# board.net
KiCad netlist of a schematic drawn in EAGLE
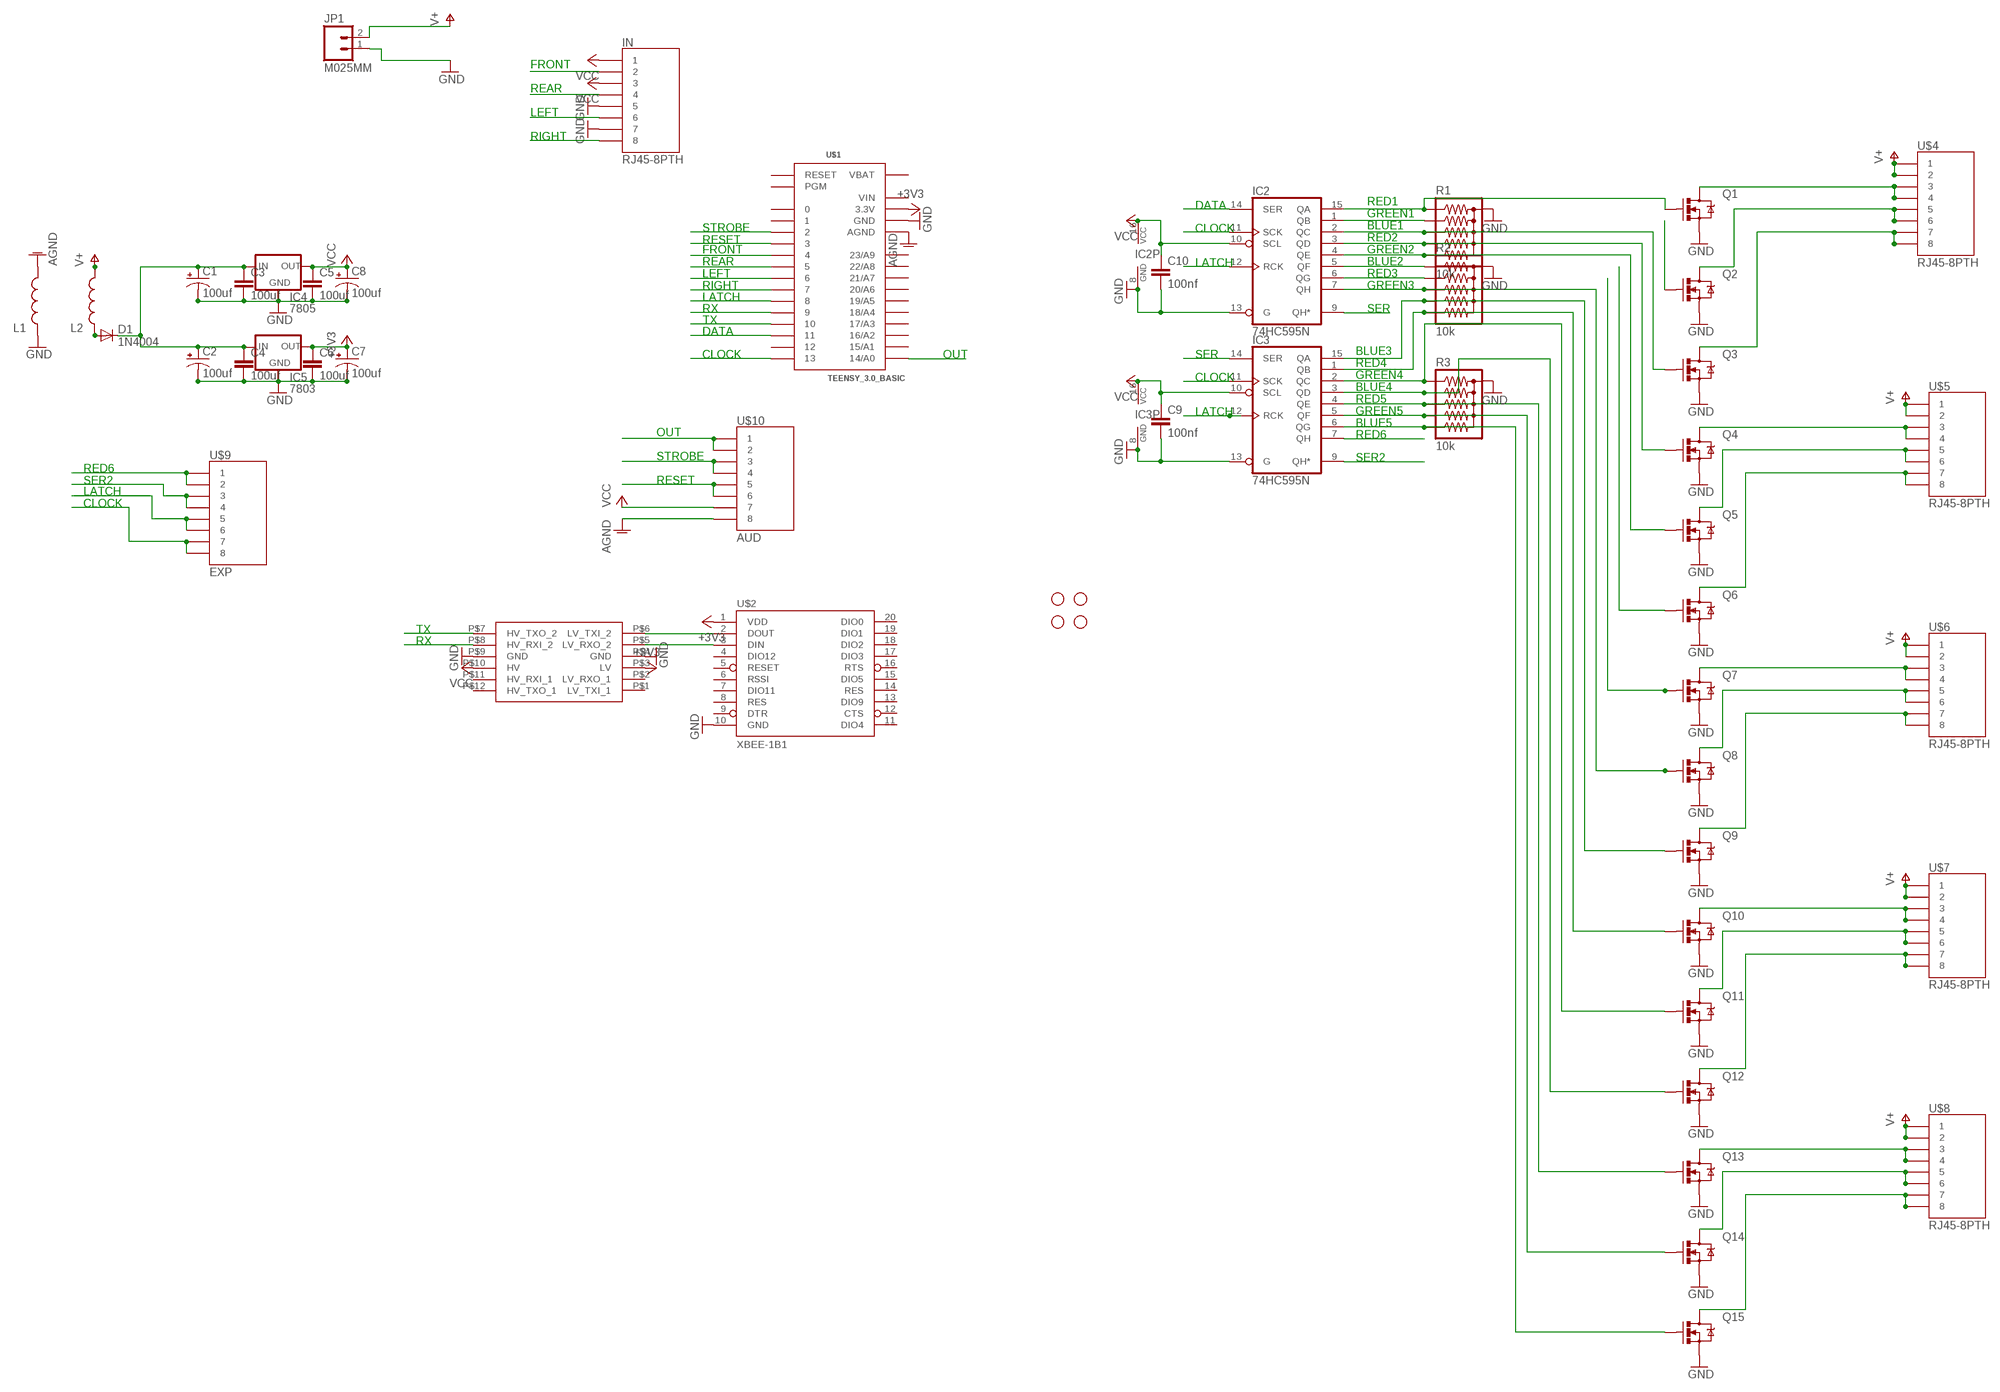
[diagram p0: schematic, sheet 1]

(export (version "E")
  (design (tool "Eeschema 10.0.6"))
  (components
    (comp (ref "C1")
      (value "100uf")
      (footprint "eagle-import:CPOL-RADIAL-100UF-25V")
      (libsource (lib "eagle-import") (part "CAP_POLPTH1"))
    )
    (comp (ref "C2")
      (value "100uf")
      (footprint "eagle-import:CPOL-RADIAL-100UF-25V")
      (libsource (lib "eagle-import") (part "CAP_POLPTH1"))
    )
    (comp (ref "C3")
      (value "100uf")
      (footprint "eagle-import:CAP-PTH-SMALL")
      (libsource (lib "eagle-import") (part "CAPPTH"))
    )
    (comp (ref "C4")
      (value "100uf")
      (footprint "eagle-import:CAP-PTH-SMALL")
      (libsource (lib "eagle-import") (part "CAPPTH"))
    )
    (comp (ref "C5")
      (value "100uf")
      (footprint "eagle-import:CAP-PTH-SMALL")
      (libsource (lib "eagle-import") (part "CAPPTH"))
    )
    (comp (ref "C6")
      (value "100uf")
      (footprint "eagle-import:CAP-PTH-SMALL")
      (libsource (lib "eagle-import") (part "CAPPTH"))
    )
    (comp (ref "C7")
      (value "100uf")
      (footprint "eagle-import:CPOL-RADIAL-100UF-25V")
      (libsource (lib "eagle-import") (part "CAP_POLPTH1"))
    )
    (comp (ref "C8")
      (value "100uf")
      (footprint "eagle-import:CPOL-RADIAL-100UF-25V")
      (libsource (lib "eagle-import") (part "CAP_POLPTH1"))
    )
    (comp (ref "C9")
      (value "100nf")
      (footprint "eagle-import:CAP-PTH-SMALL")
      (libsource (lib "eagle-import") (part "CAPPTH"))
    )
    (comp (ref "C10")
      (value "100nf")
      (footprint "eagle-import:CAP-PTH-SMALL")
      (libsource (lib "eagle-import") (part "CAPPTH"))
    )
    (comp (ref "D1")
      (value "1N4004")
      (footprint "eagle-import:DO41-10")
      (libsource (lib "eagle-import") (part "1N4004"))
    )
    (comp (ref "IC2")
      (value "74HC595N")
      (footprint "eagle-import:DIL16")
      (libsource (lib "eagle-import") (part "74595NHC"))
    )
    (comp (ref "IC3")
      (value "74HC595N")
      (footprint "eagle-import:DIL16")
      (libsource (lib "eagle-import") (part "74595NHC"))
    )
    (comp (ref "IC4")
      (value "7805")
      (footprint "eagle-import:TO220-IGO")
      (libsource (lib "eagle-import") (part "V_REG_78XXSINK"))
    )
    (comp (ref "IC5")
      (value "7803")
      (footprint "eagle-import:78XXL")
      (libsource (lib "eagle-import") (part "V_REG_LD1117VXX"))
    )
    (comp (ref "IN")
      (value "RJ45-8PTH")
      (footprint "eagle-import:RJ45-8")
      (libsource (lib "eagle-import") (part "RJ45-8PTH"))
    )
    (comp (ref "JP1")
      (value "M025MM")
      (footprint "eagle-import:SCREWTERMINAL-5MM-2")
      (libsource (lib "eagle-import") (part "M025MM"))
    )
    (comp (ref "L1")
      (value "INDUCTORRLB0912")
      (footprint "eagle-import:RLB0912")
      (libsource (lib "eagle-import") (part "INDUCTORRLB0912"))
    )
    (comp (ref "L2")
      (value "INDUCTORRLB0912")
      (footprint "eagle-import:RLB0912")
      (libsource (lib "eagle-import") (part "INDUCTORRLB0912"))
    )
    (comp (ref "Q1")
      (value "MOSFET-NCHANNELFQP30N06L")
      (footprint "eagle-import:TO220V")
      (libsource (lib "eagle-import") (part "MOSFET-NCHANNELFQP30N06L"))
    )
    (comp (ref "Q2")
      (value "MOSFET-NCHANNELFQP30N06L")
      (footprint "eagle-import:TO220V")
      (libsource (lib "eagle-import") (part "MOSFET-NCHANNELFQP30N06L"))
    )
    (comp (ref "Q3")
      (value "MOSFET-NCHANNELFQP30N06L")
      (footprint "eagle-import:TO220V")
      (libsource (lib "eagle-import") (part "MOSFET-NCHANNELFQP30N06L"))
    )
    (comp (ref "Q4")
      (value "MOSFET-NCHANNELFQP30N06L")
      (footprint "eagle-import:TO220V")
      (libsource (lib "eagle-import") (part "MOSFET-NCHANNELFQP30N06L"))
    )
    (comp (ref "Q5")
      (value "MOSFET-NCHANNELFQP30N06L")
      (footprint "eagle-import:TO220V")
      (libsource (lib "eagle-import") (part "MOSFET-NCHANNELFQP30N06L"))
    )
    (comp (ref "Q6")
      (value "MOSFET-NCHANNELFQP30N06L")
      (footprint "eagle-import:TO220V")
      (libsource (lib "eagle-import") (part "MOSFET-NCHANNELFQP30N06L"))
    )
    (comp (ref "Q7")
      (value "MOSFET-NCHANNELFQP30N06L")
      (footprint "eagle-import:TO220V")
      (libsource (lib "eagle-import") (part "MOSFET-NCHANNELFQP30N06L"))
    )
    (comp (ref "Q8")
      (value "MOSFET-NCHANNELFQP30N06L")
      (footprint "eagle-import:TO220V")
      (libsource (lib "eagle-import") (part "MOSFET-NCHANNELFQP30N06L"))
    )
    (comp (ref "Q9")
      (value "MOSFET-NCHANNELFQP30N06L")
      (footprint "eagle-import:TO220V")
      (libsource (lib "eagle-import") (part "MOSFET-NCHANNELFQP30N06L"))
    )
    (comp (ref "Q10")
      (value "MOSFET-NCHANNELFQP30N06L")
      (footprint "eagle-import:TO220V")
      (libsource (lib "eagle-import") (part "MOSFET-NCHANNELFQP30N06L"))
    )
    (comp (ref "Q11")
      (value "MOSFET-NCHANNELFQP30N06L")
      (footprint "eagle-import:TO220V")
      (libsource (lib "eagle-import") (part "MOSFET-NCHANNELFQP30N06L"))
    )
    (comp (ref "Q12")
      (value "MOSFET-NCHANNELFQP30N06L")
      (footprint "eagle-import:TO220V")
      (libsource (lib "eagle-import") (part "MOSFET-NCHANNELFQP30N06L"))
    )
    (comp (ref "Q13")
      (value "MOSFET-NCHANNELFQP30N06L")
      (footprint "eagle-import:TO220V")
      (libsource (lib "eagle-import") (part "MOSFET-NCHANNELFQP30N06L"))
    )
    (comp (ref "Q14")
      (value "MOSFET-NCHANNELFQP30N06L")
      (footprint "eagle-import:TO220V")
      (libsource (lib "eagle-import") (part "MOSFET-NCHANNELFQP30N06L"))
    )
    (comp (ref "Q15")
      (value "MOSFET-NCHANNELFQP30N06L")
      (footprint "eagle-import:TO220V")
      (libsource (lib "eagle-import") (part "MOSFET-NCHANNELFQP30N06L"))
    )
    (comp (ref "R1")
      (value "10k")
      (footprint "eagle-import:RPACK-SIP-PTH-5")
      (libsource (lib "eagle-import") (part "RPACK-BUSSED-5-SIP-PTH-5"))
    )
    (comp (ref "R2")
      (value "10k")
      (footprint "eagle-import:RPACK-SIP-PTH-5")
      (libsource (lib "eagle-import") (part "RPACK-BUSSED-5-SIP-PTH-5"))
    )
    (comp (ref "R3")
      (value "10k")
      (footprint "eagle-import:RPACK-SIP-PTH-5")
      (libsource (lib "eagle-import") (part "RPACK-BUSSED-5-SIP-PTH-5"))
    )
    (comp (ref "STANDOFF1")
      (value "STAND-OFF")
      (footprint "eagle-import:STAND-OFF")
      (libsource (lib "eagle-import") (part "STAND-OFF"))
    )
    (comp (ref "STANDOFF2")
      (value "STAND-OFF")
      (footprint "eagle-import:STAND-OFF")
      (libsource (lib "eagle-import") (part "STAND-OFF"))
    )
    (comp (ref "STANDOFF3")
      (value "STAND-OFF")
      (footprint "eagle-import:STAND-OFF")
      (libsource (lib "eagle-import") (part "STAND-OFF"))
    )
    (comp (ref "STANDOFF4")
      (value "STAND-OFF")
      (footprint "eagle-import:STAND-OFF")
      (libsource (lib "eagle-import") (part "STAND-OFF"))
    )
    (comp (ref "U$1")
      (value "TEENSY_3.0_BASIC")
      (footprint "eagle-import:TEENSY_3.0_BASIC")
      (libsource (lib "eagle-import") (part "TEENSY_3.0_BASIC"))
    )
    (comp (ref "U$2")
      (value "XBEE-1B1")
      (footprint "eagle-import:XBEE-1")
      (libsource (lib "eagle-import") (part "XBEE-1B1"))
    )
    (comp (ref "U$3")
      (value "LOGIC_LEVEL_CONVERTER")
      (footprint "eagle-import:LOGIC_LEVEL_CONVERTER")
      (libsource (lib "eagle-import") (part "LOGIC_LEVEL_CONVERTER"))
    )
    (comp (ref "U$4")
      (value "RJ45-8PTH")
      (footprint "eagle-import:RJ45-8")
      (libsource (lib "eagle-import") (part "RJ45-8PTH"))
    )
    (comp (ref "U$5")
      (value "RJ45-8PTH")
      (footprint "eagle-import:RJ45-8")
      (libsource (lib "eagle-import") (part "RJ45-8PTH"))
    )
    (comp (ref "U$6")
      (value "RJ45-8PTH")
      (footprint "eagle-import:RJ45-8")
      (libsource (lib "eagle-import") (part "RJ45-8PTH"))
    )
    (comp (ref "U$7")
      (value "RJ45-8PTH")
      (footprint "eagle-import:RJ45-8")
      (libsource (lib "eagle-import") (part "RJ45-8PTH"))
    )
    (comp (ref "U$8")
      (value "RJ45-8PTH")
      (footprint "eagle-import:RJ45-8")
      (libsource (lib "eagle-import") (part "RJ45-8PTH"))
    )
    (comp (ref "U$9")
      (value "EXP")
      (footprint "eagle-import:RJ45-8")
      (libsource (lib "eagle-import") (part "RJ45-8PTH"))
    )
    (comp (ref "U$10")
      (value "AUD")
      (footprint "eagle-import:RJ45-8")
      (libsource (lib "eagle-import") (part "RJ45-8PTH"))
    )
  )
  (nets
    (net (code "1") (name "+3V3") (class "Default")
      (node (ref "C6") (pin "1") (pinfunction "1_1") (pintype "passive"))
      (node (ref "C7") (pin "1") (pinfunction "+_1") (pintype "passive"))
      (node (ref "IC5") (pin "GND") (pinfunction "OUT_GND") (pintype "output"))
      (node (ref "U$1") (pin "3.3V") (pinfunction "3.3V_3.3V") (pintype "power_in"))
      (node (ref "U$1") (pin "3.3V1") (pinfunction "3.3V_3.3V1") (pintype "power_in"))
      (node (ref "U$2") (pin "1") (pinfunction "VDD_1") (pintype "power_in"))
      (node (ref "U$3") (pin "P$3") (pinfunction "LV_P$3") (pintype "bidirectional"))
    )
    (net (code "2") (name "/BLUE2") (class "Default")
      (node (ref "IC2") (pin "5") (pinfunction "QF_5") (pintype "tri_state"))
      (node (ref "Q6") (pin "1") (pinfunction "G_1") (pintype "passive"))
      (node (ref "R2") (pin "P$2") (pinfunction "2_P$2") (pintype "passive"))
    )
    (net (code "3") (name "/CLOCK") (class "Default")
      (node (ref "IC2") (pin "11") (pinfunction "SCK_11") (pintype "input"))
      (node (ref "IC3") (pin "11") (pinfunction "SCK_11") (pintype "input"))
      (node (ref "U$1") (pin "13") (pinfunction "13_13") (pintype "bidirectional"))
      (node (ref "U$9") (pin "7") (pinfunction "7_7") (pintype "bidirectional"))
      (node (ref "U$9") (pin "8") (pinfunction "8_8") (pintype "bidirectional"))
    )
    (net (code "4") (name "/DATA") (class "Default")
      (node (ref "IC2") (pin "14") (pinfunction "SER_14") (pintype "input"))
      (node (ref "U$1") (pin "11") (pinfunction "11_11") (pintype "bidirectional"))
    )
    (net (code "5") (name "/FRONT") (class "Default")
      (node (ref "IN") (pin "2") (pinfunction "2_2") (pintype "bidirectional"))
      (node (ref "U$1") (pin "4") (pinfunction "4_4") (pintype "bidirectional"))
    )
    (net (code "6") (name "/GREEN1") (class "Default")
      (node (ref "IC2") (pin "1") (pinfunction "QB_1") (pintype "tri_state"))
      (node (ref "Q2") (pin "1") (pinfunction "G_1") (pintype "passive"))
      (node (ref "R1") (pin "P$3") (pinfunction "3_P$3") (pintype "passive"))
    )
    (net (code "7") (name "/LATCH") (class "Default")
      (node (ref "IC2") (pin "12") (pinfunction "RCK_12") (pintype "input"))
      (node (ref "IC3") (pin "12") (pinfunction "RCK_12") (pintype "input"))
      (node (ref "U$1") (pin "8") (pinfunction "8_8") (pintype "bidirectional"))
      (node (ref "U$9") (pin "5") (pinfunction "5_5") (pintype "bidirectional"))
      (node (ref "U$9") (pin "6") (pinfunction "6_6") (pintype "bidirectional"))
    )
    (net (code "8") (name "/LEFT") (class "Default")
      (node (ref "IN") (pin "6") (pinfunction "6_6") (pintype "bidirectional"))
      (node (ref "U$1") (pin "6") (pinfunction "6_6") (pintype "bidirectional"))
    )
    (net (code "9") (name "/OUT") (class "Default")
      (node (ref "U$1") (pin "14/A0") (pinfunction "14/A0_14/A0") (pintype "bidirectional"))
      (node (ref "U$10") (pin "1") (pinfunction "1_1") (pintype "bidirectional"))
      (node (ref "U$10") (pin "2") (pinfunction "2_2") (pintype "bidirectional"))
    )
    (net (code "10") (name "/REAR") (class "Default")
      (node (ref "IN") (pin "4") (pinfunction "4_4") (pintype "bidirectional"))
      (node (ref "U$1") (pin "5") (pinfunction "5_5") (pintype "bidirectional"))
    )
    (net (code "11") (name "/RED3") (class "Default")
      (node (ref "IC2") (pin "6") (pinfunction "QG_6") (pintype "tri_state"))
      (node (ref "Q7") (pin "1") (pinfunction "G_1") (pintype "passive"))
      (node (ref "R2") (pin "P$3") (pinfunction "3_P$3") (pintype "passive"))
    )
    (net (code "12") (name "/RED6") (class "Default")
      (node (ref "IC3") (pin "7") (pinfunction "QH_7") (pintype "tri_state"))
      (node (ref "U$9") (pin "1") (pinfunction "1_1") (pintype "bidirectional"))
      (node (ref "U$9") (pin "2") (pinfunction "2_2") (pintype "bidirectional"))
    )
    (net (code "13") (name "/RESET") (class "Default")
      (node (ref "U$1") (pin "3") (pinfunction "3_3") (pintype "bidirectional"))
      (node (ref "U$10") (pin "5") (pinfunction "5_5") (pintype "bidirectional"))
      (node (ref "U$10") (pin "6") (pinfunction "6_6") (pintype "bidirectional"))
    )
    (net (code "14") (name "/RIGHT") (class "Default")
      (node (ref "IN") (pin "8") (pinfunction "8_8") (pintype "bidirectional"))
      (node (ref "U$1") (pin "7") (pinfunction "7_7") (pintype "bidirectional"))
    )
    (net (code "15") (name "/RX") (class "Default")
      (node (ref "U$1") (pin "9") (pinfunction "9_9") (pintype "bidirectional"))
      (node (ref "U$3") (pin "P$7") (pinfunction "HV_TXO_2_P$7") (pintype "bidirectional"))
    )
    (net (code "16") (name "/SER") (class "Default")
      (node (ref "IC2") (pin "9") (pinfunction "QH*_9") (pintype "tri_state"))
      (node (ref "IC3") (pin "14") (pinfunction "SER_14") (pintype "input"))
    )
    (net (code "17") (name "/SER2") (class "Default")
      (node (ref "IC3") (pin "9") (pinfunction "QH*_9") (pintype "tri_state"))
      (node (ref "U$9") (pin "3") (pinfunction "3_3") (pintype "bidirectional"))
      (node (ref "U$9") (pin "4") (pinfunction "4_4") (pintype "bidirectional"))
    )
    (net (code "18") (name "/STROBE") (class "Default")
      (node (ref "U$1") (pin "2") (pinfunction "2_2") (pintype "bidirectional"))
      (node (ref "U$10") (pin "3") (pinfunction "3_3") (pintype "bidirectional"))
      (node (ref "U$10") (pin "4") (pinfunction "4_4") (pintype "bidirectional"))
    )
    (net (code "19") (name "/TX") (class "Default")
      (node (ref "U$1") (pin "10") (pinfunction "10_10") (pintype "bidirectional"))
      (node (ref "U$3") (pin "P$8") (pinfunction "HV_RXI_2_P$8") (pintype "bidirectional"))
    )
    (net (code "20") (name "/VBAT") (class "Default")
      (node (ref "U$1") (pin "VBAT") (pinfunction "VBAT_VBAT") (pintype "power_in"))
    )
    (net (code "21") (name "/VIN") (class "Default")
      (node (ref "U$1") (pin "VIN") (pinfunction "VIN_VIN") (pintype "power_in"))
    )
    (net (code "22") (name "AGND") (class "Default")
      (node (ref "L1") (pin "2") (pinfunction "2_2") (pintype "passive"))
      (node (ref "U$1") (pin "AGND") (pinfunction "AGND_AGND") (pintype "power_in"))
      (node (ref "U$10") (pin "8") (pinfunction "8_8") (pintype "bidirectional"))
    )
    (net (code "23") (name "GND") (class "Default")
      (node (ref "C1") (pin "2") (pinfunction "-_2") (pintype "passive"))
      (node (ref "C10") (pin "2") (pinfunction "2_2") (pintype "passive"))
      (node (ref "C2") (pin "2") (pinfunction "-_2") (pintype "passive"))
      (node (ref "C3") (pin "2") (pinfunction "2_2") (pintype "passive"))
      (node (ref "C4") (pin "2") (pinfunction "2_2") (pintype "passive"))
      (node (ref "C5") (pin "2") (pinfunction "2_2") (pintype "passive"))
      (node (ref "C6") (pin "2") (pinfunction "2_2") (pintype "passive"))
      (node (ref "C7") (pin "2") (pinfunction "-_2") (pintype "passive"))
      (node (ref "C8") (pin "2") (pinfunction "-_2") (pintype "passive"))
      (node (ref "C9") (pin "2") (pinfunction "2_2") (pintype "passive"))
      (node (ref "IC2") (pin "13") (pinfunction "G_13") (pintype "input"))
      (node (ref "IC2") (pin "8") (pinfunction "GND_8") (pintype "power_in"))
      (node (ref "IC3") (pin "13") (pinfunction "G_13") (pintype "input"))
      (node (ref "IC3") (pin "8") (pinfunction "GND_8") (pintype "power_in"))
      (node (ref "IC4") (pin "GND") (pinfunction "GND_GND") (pintype "input"))
      (node (ref "IC5") (pin "IN") (pinfunction "GND_IN") (pintype "input"))
      (node (ref "IN") (pin "5") (pinfunction "5_5") (pintype "bidirectional"))
      (node (ref "IN") (pin "7") (pinfunction "7_7") (pintype "bidirectional"))
      (node (ref "JP1") (pin "1") (pinfunction "1_1") (pintype "passive"))
      (node (ref "L1") (pin "1") (pinfunction "1_1") (pintype "passive"))
      (node (ref "Q1") (pin "3") (pinfunction "S_3") (pintype "passive"))
      (node (ref "Q10") (pin "3") (pinfunction "S_3") (pintype "passive"))
      (node (ref "Q11") (pin "3") (pinfunction "S_3") (pintype "passive"))
      (node (ref "Q12") (pin "3") (pinfunction "S_3") (pintype "passive"))
      (node (ref "Q13") (pin "3") (pinfunction "S_3") (pintype "passive"))
      (node (ref "Q14") (pin "3") (pinfunction "S_3") (pintype "passive"))
      (node (ref "Q15") (pin "3") (pinfunction "S_3") (pintype "passive"))
      (node (ref "Q2") (pin "3") (pinfunction "S_3") (pintype "passive"))
      (node (ref "Q3") (pin "3") (pinfunction "S_3") (pintype "passive"))
      (node (ref "Q4") (pin "3") (pinfunction "S_3") (pintype "passive"))
      (node (ref "Q5") (pin "3") (pinfunction "S_3") (pintype "passive"))
      (node (ref "Q6") (pin "3") (pinfunction "S_3") (pintype "passive"))
      (node (ref "Q7") (pin "3") (pinfunction "S_3") (pintype "passive"))
      (node (ref "Q8") (pin "3") (pinfunction "S_3") (pintype "passive"))
      (node (ref "Q9") (pin "3") (pinfunction "S_3") (pintype "passive"))
      (node (ref "R1") (pin "P$1") (pinfunction "1_P$1") (pintype "passive"))
      (node (ref "R2") (pin "P$1") (pinfunction "1_P$1") (pintype "passive"))
      (node (ref "R3") (pin "P$1") (pinfunction "1_P$1") (pintype "passive"))
      (node (ref "U$1") (pin "GND") (pinfunction "GND_GND") (pintype "power_in"))
      (node (ref "U$1") (pin "GND1") (pinfunction "GND_GND1") (pintype "power_in"))
      (node (ref "U$2") (pin "10") (pinfunction "GND_10") (pintype "power_in"))
      (node (ref "U$3") (pin "P$4") (pinfunction "GND_P$4") (pintype "bidirectional"))
      (node (ref "U$3") (pin "P$9") (pinfunction "GND_P$9") (pintype "bidirectional"))
    )
    (net (code "24") (name "Net-(C1-+)") (class "Default")
      (node (ref "C1") (pin "1") (pinfunction "+_1") (pintype "passive"))
      (node (ref "C2") (pin "1") (pinfunction "+_1") (pintype "passive"))
      (node (ref "C3") (pin "1") (pinfunction "1_1") (pintype "passive"))
      (node (ref "C4") (pin "1") (pinfunction "1_1") (pintype "passive"))
      (node (ref "D1") (pin "C") (pinfunction "C_C") (pintype "passive"))
      (node (ref "IC4") (pin "IN") (pinfunction "IN_IN") (pintype "input"))
      (node (ref "IC5") (pin "OUT") (pinfunction "IN_OUT") (pintype "input"))
    )
    (net (code "25") (name "Net-(D1-PadA)") (class "Default")
      (node (ref "D1") (pin "A") (pinfunction "A_A") (pintype "passive"))
      (node (ref "L2") (pin "1") (pinfunction "1_1") (pintype "passive"))
    )
    (net (code "26") (name "Net-(IC2A-QA)") (class "Default")
      (node (ref "IC2") (pin "15") (pinfunction "QA_15") (pintype "tri_state"))
      (node (ref "Q1") (pin "1") (pinfunction "G_1") (pintype "passive"))
      (node (ref "R1") (pin "P$2") (pinfunction "2_P$2") (pintype "passive"))
    )
    (net (code "27") (name "Net-(IC2A-QC)") (class "Default")
      (node (ref "IC2") (pin "2") (pinfunction "QC_2") (pintype "tri_state"))
      (node (ref "Q3") (pin "1") (pinfunction "G_1") (pintype "passive"))
      (node (ref "R1") (pin "P$4") (pinfunction "4_P$4") (pintype "passive"))
    )
    (net (code "28") (name "Net-(IC2A-QD)") (class "Default")
      (node (ref "IC2") (pin "3") (pinfunction "QD_3") (pintype "tri_state"))
      (node (ref "Q4") (pin "1") (pinfunction "G_1") (pintype "passive"))
      (node (ref "R1") (pin "P$5") (pinfunction "5_P$5") (pintype "passive"))
    )
    (net (code "29") (name "Net-(IC2A-QE)") (class "Default")
      (node (ref "IC2") (pin "4") (pinfunction "QE_4") (pintype "tri_state"))
      (node (ref "Q5") (pin "1") (pinfunction "G_1") (pintype "passive"))
      (node (ref "R1") (pin "P$6") (pinfunction "6_P$6") (pintype "passive"))
    )
    (net (code "30") (name "Net-(IC2A-QH)") (class "Default")
      (node (ref "IC2") (pin "7") (pinfunction "QH_7") (pintype "tri_state"))
      (node (ref "Q8") (pin "1") (pinfunction "G_1") (pintype "passive"))
      (node (ref "R2") (pin "P$4") (pinfunction "4_P$4") (pintype "passive"))
    )
    (net (code "31") (name "Net-(IC3A-QA)") (class "Default")
      (node (ref "IC3") (pin "15") (pinfunction "QA_15") (pintype "tri_state"))
      (node (ref "Q9") (pin "1") (pinfunction "G_1") (pintype "passive"))
      (node (ref "R2") (pin "P$5") (pinfunction "5_P$5") (pintype "passive"))
    )
    (net (code "32") (name "Net-(IC3A-QB)") (class "Default")
      (node (ref "IC3") (pin "1") (pinfunction "QB_1") (pintype "tri_state"))
      (node (ref "Q10") (pin "1") (pinfunction "G_1") (pintype "passive"))
      (node (ref "R2") (pin "P$6") (pinfunction "6_P$6") (pintype "passive"))
    )
    (net (code "33") (name "Net-(IC3A-QC)") (class "Default")
      (node (ref "IC3") (pin "2") (pinfunction "QC_2") (pintype "tri_state"))
      (node (ref "Q11") (pin "1") (pinfunction "G_1") (pintype "passive"))
      (node (ref "R3") (pin "P$2") (pinfunction "2_P$2") (pintype "passive"))
    )
    (net (code "34") (name "Net-(IC3A-QD)") (class "Default")
      (node (ref "IC3") (pin "3") (pinfunction "QD_3") (pintype "tri_state"))
      (node (ref "Q12") (pin "1") (pinfunction "G_1") (pintype "passive"))
      (node (ref "R3") (pin "P$3") (pinfunction "3_P$3") (pintype "passive"))
    )
    (net (code "35") (name "Net-(IC3A-QE)") (class "Default")
      (node (ref "IC3") (pin "4") (pinfunction "QE_4") (pintype "tri_state"))
      (node (ref "Q13") (pin "1") (pinfunction "G_1") (pintype "passive"))
      (node (ref "R3") (pin "P$4") (pinfunction "4_P$4") (pintype "passive"))
    )
    (net (code "36") (name "Net-(IC3A-QF)") (class "Default")
      (node (ref "IC3") (pin "5") (pinfunction "QF_5") (pintype "tri_state"))
      (node (ref "Q14") (pin "1") (pinfunction "G_1") (pintype "passive"))
      (node (ref "R3") (pin "P$5") (pinfunction "5_P$5") (pintype "passive"))
    )
    (net (code "37") (name "Net-(IC3A-QG)") (class "Default")
      (node (ref "IC3") (pin "6") (pinfunction "QG_6") (pintype "tri_state"))
      (node (ref "Q15") (pin "1") (pinfunction "G_1") (pintype "passive"))
      (node (ref "R3") (pin "P$6") (pinfunction "6_P$6") (pintype "passive"))
    )
    (net (code "38") (name "Net-(Q1-D)") (class "Default")
      (node (ref "Q1") (pin "2") (pinfunction "D_2") (pintype "passive"))
      (node (ref "U$4") (pin "3") (pinfunction "3_3") (pintype "bidirectional"))
      (node (ref "U$4") (pin "4") (pinfunction "4_4") (pintype "bidirectional"))
    )
    (net (code "39") (name "Net-(Q2-D)") (class "Default")
      (node (ref "Q2") (pin "2") (pinfunction "D_2") (pintype "passive"))
      (node (ref "U$4") (pin "5") (pinfunction "5_5") (pintype "bidirectional"))
      (node (ref "U$4") (pin "6") (pinfunction "6_6") (pintype "bidirectional"))
    )
    (net (code "40") (name "Net-(Q3-D)") (class "Default")
      (node (ref "Q3") (pin "2") (pinfunction "D_2") (pintype "passive"))
      (node (ref "U$4") (pin "7") (pinfunction "7_7") (pintype "bidirectional"))
      (node (ref "U$4") (pin "8") (pinfunction "8_8") (pintype "bidirectional"))
    )
    (net (code "41") (name "Net-(Q4-D)") (class "Default")
      (node (ref "Q4") (pin "2") (pinfunction "D_2") (pintype "passive"))
      (node (ref "U$5") (pin "3") (pinfunction "3_3") (pintype "bidirectional"))
      (node (ref "U$5") (pin "4") (pinfunction "4_4") (pintype "bidirectional"))
    )
    (net (code "42") (name "Net-(Q5-D)") (class "Default")
      (node (ref "Q5") (pin "2") (pinfunction "D_2") (pintype "passive"))
      (node (ref "U$5") (pin "5") (pinfunction "5_5") (pintype "bidirectional"))
      (node (ref "U$5") (pin "6") (pinfunction "6_6") (pintype "bidirectional"))
    )
    (net (code "43") (name "Net-(Q6-D)") (class "Default")
      (node (ref "Q6") (pin "2") (pinfunction "D_2") (pintype "passive"))
      (node (ref "U$5") (pin "7") (pinfunction "7_7") (pintype "bidirectional"))
      (node (ref "U$5") (pin "8") (pinfunction "8_8") (pintype "bidirectional"))
    )
    (net (code "44") (name "Net-(Q7-D)") (class "Default")
      (node (ref "Q7") (pin "2") (pinfunction "D_2") (pintype "passive"))
      (node (ref "U$6") (pin "3") (pinfunction "3_3") (pintype "bidirectional"))
      (node (ref "U$6") (pin "4") (pinfunction "4_4") (pintype "bidirectional"))
    )
    (net (code "45") (name "Net-(Q8-D)") (class "Default")
      (node (ref "Q8") (pin "2") (pinfunction "D_2") (pintype "passive"))
      (node (ref "U$6") (pin "5") (pinfunction "5_5") (pintype "bidirectional"))
      (node (ref "U$6") (pin "6") (pinfunction "6_6") (pintype "bidirectional"))
    )
    (net (code "46") (name "Net-(Q9-D)") (class "Default")
      (node (ref "Q9") (pin "2") (pinfunction "D_2") (pintype "passive"))
      (node (ref "U$6") (pin "7") (pinfunction "7_7") (pintype "bidirectional"))
      (node (ref "U$6") (pin "8") (pinfunction "8_8") (pintype "bidirectional"))
    )
    (net (code "47") (name "Net-(Q10-D)") (class "Default")
      (node (ref "Q10") (pin "2") (pinfunction "D_2") (pintype "passive"))
      (node (ref "U$7") (pin "3") (pinfunction "3_3") (pintype "bidirectional"))
      (node (ref "U$7") (pin "4") (pinfunction "4_4") (pintype "bidirectional"))
    )
    (net (code "48") (name "Net-(Q11-D)") (class "Default")
      (node (ref "Q11") (pin "2") (pinfunction "D_2") (pintype "passive"))
      (node (ref "U$7") (pin "5") (pinfunction "5_5") (pintype "bidirectional"))
      (node (ref "U$7") (pin "6") (pinfunction "6_6") (pintype "bidirectional"))
    )
    (net (code "49") (name "Net-(Q12-D)") (class "Default")
      (node (ref "Q12") (pin "2") (pinfunction "D_2") (pintype "passive"))
      (node (ref "U$7") (pin "7") (pinfunction "7_7") (pintype "bidirectional"))
      (node (ref "U$7") (pin "8") (pinfunction "8_8") (pintype "bidirectional"))
    )
    (net (code "50") (name "Net-(Q13-D)") (class "Default")
      (node (ref "Q13") (pin "2") (pinfunction "D_2") (pintype "passive"))
      (node (ref "U$8") (pin "3") (pinfunction "3_3") (pintype "bidirectional"))
      (node (ref "U$8") (pin "4") (pinfunction "4_4") (pintype "bidirectional"))
    )
    (net (code "51") (name "Net-(Q14-D)") (class "Default")
      (node (ref "Q14") (pin "2") (pinfunction "D_2") (pintype "passive"))
      (node (ref "U$8") (pin "5") (pinfunction "5_5") (pintype "bidirectional"))
      (node (ref "U$8") (pin "6") (pinfunction "6_6") (pintype "bidirectional"))
    )
    (net (code "52") (name "Net-(Q15-D)") (class "Default")
      (node (ref "Q15") (pin "2") (pinfunction "D_2") (pintype "passive"))
      (node (ref "U$8") (pin "7") (pinfunction "7_7") (pintype "bidirectional"))
      (node (ref "U$8") (pin "8") (pinfunction "8_8") (pintype "bidirectional"))
    )
    (net (code "53") (name "Net-(U$2-DIN)") (class "Default")
      (node (ref "U$2") (pin "3") (pinfunction "DIN_3") (pintype "input"))
      (node (ref "U$3") (pin "P$5") (pinfunction "LV_RXO_2_P$5") (pintype "bidirectional"))
    )
    (net (code "54") (name "Net-(U$2-DOUT)") (class "Default")
      (node (ref "U$2") (pin "2") (pinfunction "DOUT_2") (pintype "output"))
      (node (ref "U$3") (pin "P$6") (pinfunction "LV_TXI_2_P$6") (pintype "bidirectional"))
    )
    (net (code "55") (name "V+") (class "Default")
      (node (ref "JP1") (pin "2") (pinfunction "2_2") (pintype "passive"))
      (node (ref "L2") (pin "2") (pinfunction "2_2") (pintype "passive"))
      (node (ref "U$4") (pin "1") (pinfunction "1_1") (pintype "bidirectional"))
      (node (ref "U$4") (pin "2") (pinfunction "2_2") (pintype "bidirectional"))
      (node (ref "U$5") (pin "1") (pinfunction "1_1") (pintype "bidirectional"))
      (node (ref "U$5") (pin "2") (pinfunction "2_2") (pintype "bidirectional"))
      (node (ref "U$6") (pin "1") (pinfunction "1_1") (pintype "bidirectional"))
      (node (ref "U$6") (pin "2") (pinfunction "2_2") (pintype "bidirectional"))
      (node (ref "U$7") (pin "1") (pinfunction "1_1") (pintype "bidirectional"))
      (node (ref "U$7") (pin "2") (pinfunction "2_2") (pintype "bidirectional"))
      (node (ref "U$8") (pin "1") (pinfunction "1_1") (pintype "bidirectional"))
      (node (ref "U$8") (pin "2") (pinfunction "2_2") (pintype "bidirectional"))
    )
    (net (code "56") (name "VCC") (class "Default")
      (node (ref "C10") (pin "1") (pinfunction "1_1") (pintype "passive"))
      (node (ref "C5") (pin "1") (pinfunction "1_1") (pintype "passive"))
      (node (ref "C8") (pin "1") (pinfunction "+_1") (pintype "passive"))
      (node (ref "C9") (pin "1") (pinfunction "1_1") (pintype "passive"))
      (node (ref "IC2") (pin "10") (pinfunction "SCL_10") (pintype "input"))
      (node (ref "IC2") (pin "16") (pinfunction "VCC_16") (pintype "power_in"))
      (node (ref "IC3") (pin "10") (pinfunction "SCL_10") (pintype "input"))
      (node (ref "IC3") (pin "16") (pinfunction "VCC_16") (pintype "power_in"))
      (node (ref "IC4") (pin "OUT") (pinfunction "OUT_OUT") (pintype "output"))
      (node (ref "IN") (pin "1") (pinfunction "1_1") (pintype "bidirectional"))
      (node (ref "IN") (pin "3") (pinfunction "3_3") (pintype "bidirectional"))
      (node (ref "U$10") (pin "7") (pinfunction "7_7") (pintype "bidirectional"))
      (node (ref "U$3") (pin "P$10") (pinfunction "HV_P$10") (pintype "bidirectional"))
    )
    (net (code "57") (name "unconnected-(U$1-Pad0)") (class "Default")
      (node (ref "U$1") (pin "0") (pinfunction "0_0") (pintype "bidirectional"))
    )
    (net (code "58") (name "unconnected-(U$1-Pad1)") (class "Default")
      (node (ref "U$1") (pin "1") (pinfunction "1_1") (pintype "bidirectional"))
    )
    (net (code "59") (name "unconnected-(U$1-Pad12)") (class "Default")
      (node (ref "U$1") (pin "12") (pinfunction "12_12") (pintype "bidirectional"))
    )
    (net (code "60") (name "unconnected-(U$1-Pad15{slash}A1)") (class "Default")
      (node (ref "U$1") (pin "15/A1") (pinfunction "15/A1_15/A1") (pintype "bidirectional"))
    )
    (net (code "61") (name "unconnected-(U$1-Pad16{slash}A2)") (class "Default")
      (node (ref "U$1") (pin "16/A2") (pinfunction "16/A2_16/A2") (pintype "bidirectional"))
    )
    (net (code "62") (name "unconnected-(U$1-Pad17{slash}A3)") (class "Default")
      (node (ref "U$1") (pin "17/A3") (pinfunction "17/A3_17/A3") (pintype "bidirectional"))
    )
    (net (code "63") (name "unconnected-(U$1-Pad18{slash}A4)") (class "Default")
      (node (ref "U$1") (pin "18/A4") (pinfunction "18/A4_18/A4") (pintype "bidirectional"))
    )
    (net (code "64") (name "unconnected-(U$1-Pad19{slash}A5)") (class "Default")
      (node (ref "U$1") (pin "19/A5") (pinfunction "19/A5_19/A5") (pintype "bidirectional"))
    )
    (net (code "65") (name "unconnected-(U$1-Pad20{slash}A6)") (class "Default")
      (node (ref "U$1") (pin "20/A6") (pinfunction "20/A6_20/A6") (pintype "bidirectional"))
    )
    (net (code "66") (name "unconnected-(U$1-Pad21{slash}A7)") (class "Default")
      (node (ref "U$1") (pin "21/A7") (pinfunction "21/A7_21/A7") (pintype "bidirectional"))
    )
    (net (code "67") (name "unconnected-(U$1-Pad22{slash}A8)") (class "Default")
      (node (ref "U$1") (pin "22/A8") (pinfunction "22/A8_22/A8") (pintype "bidirectional"))
    )
    (net (code "68") (name "unconnected-(U$1-Pad23{slash}A9)") (class "Default")
      (node (ref "U$1") (pin "23/A9") (pinfunction "23/A9_23/A9") (pintype "bidirectional"))
    )
    (net (code "69") (name "unconnected-(U$1-PadPGM)") (class "Default")
      (node (ref "U$1") (pin "PGM") (pinfunction "PGM_PGM") (pintype "bidirectional"))
    )
    (net (code "70") (name "unconnected-(U$1-PadRESET)") (class "Default")
      (node (ref "U$1") (pin "RESET") (pinfunction "RESET_RESET") (pintype "bidirectional"))
    )
    (net (code "71") (name "unconnected-(U$2-CTS-Pad12)") (class "Default")
      (node (ref "U$2") (pin "12") (pinfunction "CTS_12") (pintype "output"))
    )
    (net (code "72") (name "unconnected-(U$2-DIO0-Pad20)") (class "Default")
      (node (ref "U$2") (pin "20") (pinfunction "DIO0_20") (pintype "bidirectional"))
    )
    (net (code "73") (name "unconnected-(U$2-DIO1-Pad19)") (class "Default")
      (node (ref "U$2") (pin "19") (pinfunction "DIO1_19") (pintype "bidirectional"))
    )
    (net (code "74") (name "unconnected-(U$2-DIO2-Pad18)") (class "Default")
      (node (ref "U$2") (pin "18") (pinfunction "DIO2_18") (pintype "bidirectional"))
    )
    (net (code "75") (name "unconnected-(U$2-DIO3-Pad17)") (class "Default")
      (node (ref "U$2") (pin "17") (pinfunction "DIO3_17") (pintype "bidirectional"))
    )
    (net (code "76") (name "unconnected-(U$2-DIO4-Pad11)") (class "Default")
      (node (ref "U$2") (pin "11") (pinfunction "DIO4_11") (pintype "bidirectional"))
    )
    (net (code "77") (name "unconnected-(U$2-DIO5-Pad15)") (class "Default")
      (node (ref "U$2") (pin "15") (pinfunction "DIO5_15") (pintype "bidirectional"))
    )
    (net (code "78") (name "unconnected-(U$2-DIO9-Pad13)") (class "Default")
      (node (ref "U$2") (pin "13") (pinfunction "DIO9_13") (pintype "bidirectional"))
    )
    (net (code "79") (name "unconnected-(U$2-DIO11-Pad7)") (class "Default")
      (node (ref "U$2") (pin "7") (pinfunction "DIO11_7") (pintype "bidirectional"))
    )
    (net (code "80") (name "unconnected-(U$2-DIO12-Pad4)") (class "Default")
      (node (ref "U$2") (pin "4") (pinfunction "DIO12_4") (pintype "bidirectional"))
    )
    (net (code "81") (name "unconnected-(U$2-DTR-Pad9)") (class "Default")
      (node (ref "U$2") (pin "9") (pinfunction "DTR_9") (pintype "bidirectional"))
    )
    (net (code "82") (name "unconnected-(U$2-RES-Pad8)") (class "Default")
      (node (ref "U$2") (pin "8") (pinfunction "RES_8") (pintype "bidirectional"))
    )
    (net (code "83") (name "unconnected-(U$2-RES-Pad14)") (class "Default")
      (node (ref "U$2") (pin "14") (pinfunction "RES_14") (pintype "bidirectional"))
    )
    (net (code "84") (name "unconnected-(U$2-RESET-Pad5)") (class "Default")
      (node (ref "U$2") (pin "5") (pinfunction "RESET_5") (pintype "input"))
    )
    (net (code "85") (name "unconnected-(U$2-RSSI-Pad6)") (class "Default")
      (node (ref "U$2") (pin "6") (pinfunction "RSSI_6") (pintype "bidirectional"))
    )
    (net (code "86") (name "unconnected-(U$2-RTS-Pad16)") (class "Default")
      (node (ref "U$2") (pin "16") (pinfunction "RTS_16") (pintype "input"))
    )
    (net (code "87") (name "unconnected-(U$3-HV_RXI_1-PadP$11)") (class "Default")
      (node (ref "U$3") (pin "P$11") (pinfunction "HV_RXI_1_P$11") (pintype "bidirectional"))
    )
    (net (code "88") (name "unconnected-(U$3-HV_TXO_1-PadP$12)") (class "Default")
      (node (ref "U$3") (pin "P$12") (pinfunction "HV_TXO_1_P$12") (pintype "bidirectional"))
    )
    (net (code "89") (name "unconnected-(U$3-LV_RXO_1-PadP$2)") (class "Default")
      (node (ref "U$3") (pin "P$2") (pinfunction "LV_RXO_1_P$2") (pintype "bidirectional"))
    )
    (net (code "90") (name "unconnected-(U$3-LV_TXI_1-PadP$1)") (class "Default")
      (node (ref "U$3") (pin "P$1") (pinfunction "LV_TXI_1_P$1") (pintype "bidirectional"))
    )
  )
)
